# nigme1_Switch.net
KiCad netlist of a schematic drawn in Altium Designer
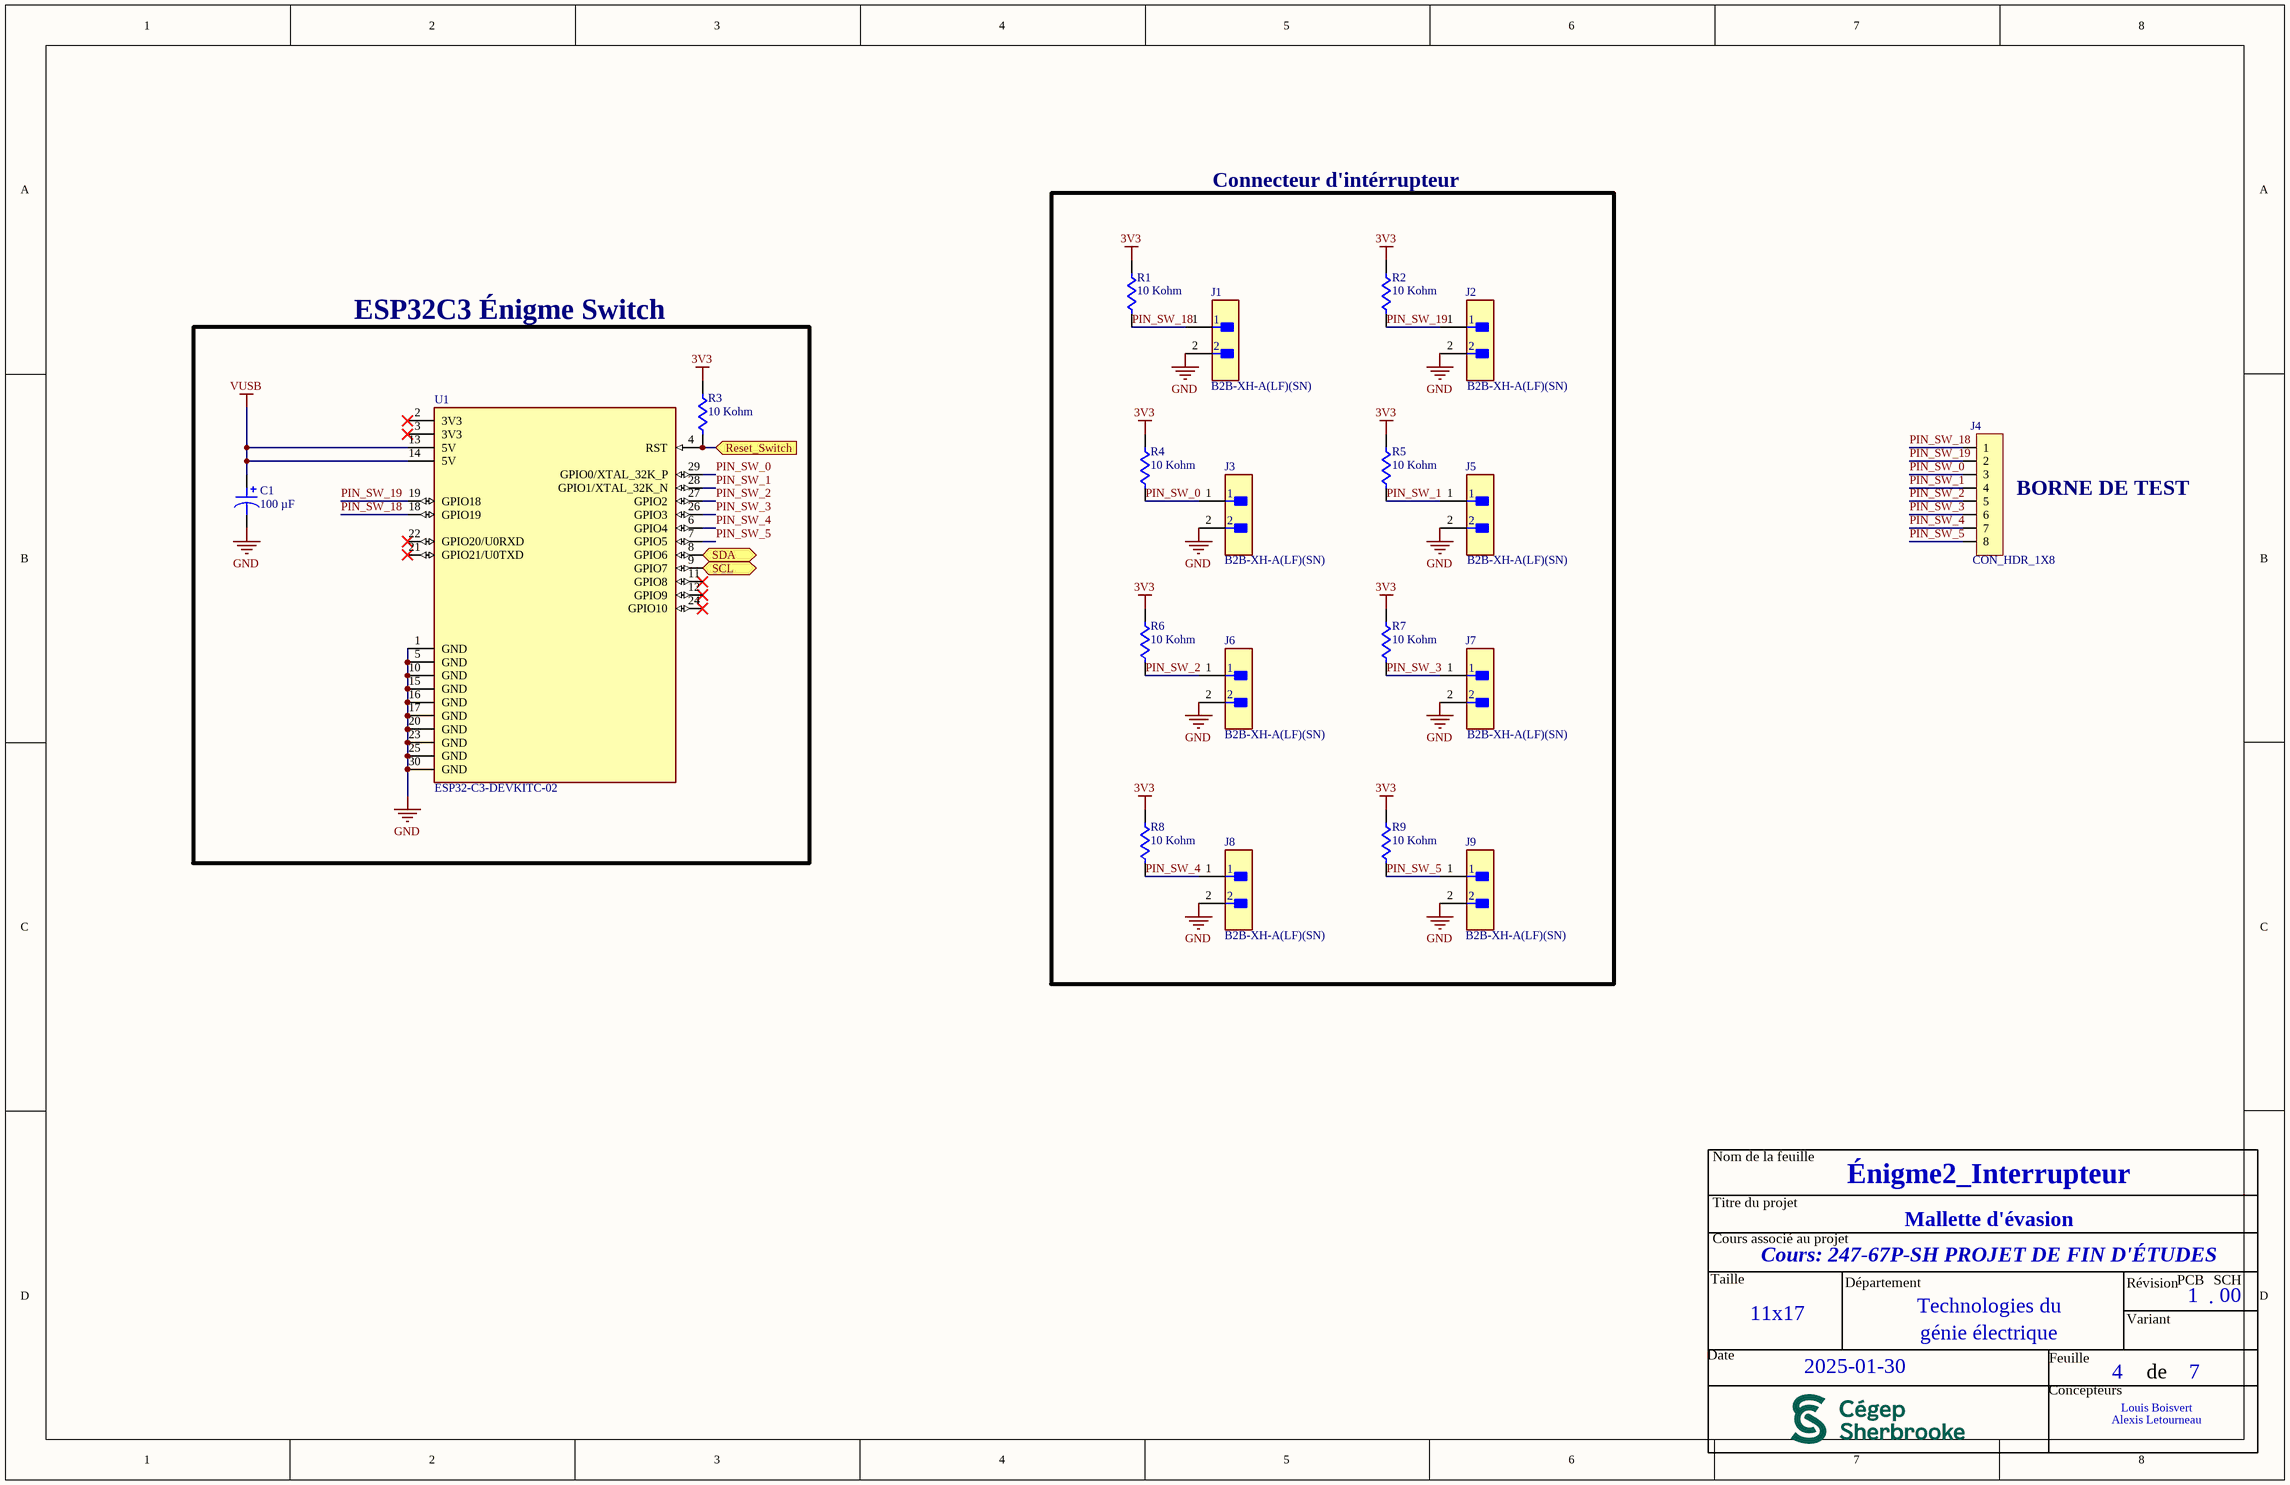
[diagram p0: Énigme1_Switch.SchDoc]

(export (version "E")
  (design (tool "Eeschema 10.0.6"))
  (components
    (comp (ref "C1")
      (value "100 µF")
      (footprint "CAP AL TH D8 L3.5 H12.5")
      (description "CAP ALUM 100UF 20% 50V RADIAL")
      (fields (field (name "PART NUMBER") "860020674015") (field (name "MANUFACTURER") "Würth Elektronik"))
      (libsource (lib "Celestial Altium Library - altium_library") (part "Polarised Capacitor"))
    )
    (comp (ref "J1")
      (value "B2B-XH-A(LF)(SN)")
      (footprint "FP-B2B-XH-A_LF_SN-MFG")
      (description "CONN HEADER VERT 2POS 2.5MM")
      (libsource (lib "Altium Content Vault") (part "3bc925449376181038e59eaffc5286c"))
    )
    (comp (ref "J2")
      (value "B2B-XH-A(LF)(SN)")
      (footprint "FP-B2B-XH-A_LF_SN-MFG")
      (description "CONN HEADER VERT 2POS 2.5MM")
      (libsource (lib "Altium Content Vault") (part "3bc925449376181038e59eaffc5286c"))
    )
    (comp (ref "J3")
      (value "B2B-XH-A(LF)(SN)")
      (footprint "FP-B2B-XH-A_LF_SN-MFG")
      (description "CONN HEADER VERT 2POS 2.5MM")
      (libsource (lib "Altium Content Vault") (part "3bc925449376181038e59eaffc5286c"))
    )
    (comp (ref "J4")
      (value "CON_HDR_1X8")
      (footprint "CON_HDR_1x8")
      (description "CON - Header 1X8 pins, 100Mils - TH-8")
      (fields (field (name "SOURCE") "CEGEP_SHERBROOKE_TGE_LIBRARY.SchLib"))
      (libsource (lib "Cegep de Sherbrooke") (part "CON_HDR_1X8"))
    )
    (comp (ref "J5")
      (value "B2B-XH-A(LF)(SN)")
      (footprint "FP-B2B-XH-A_LF_SN-MFG")
      (description "CONN HEADER VERT 2POS 2.5MM")
      (libsource (lib "Altium Content Vault") (part "3bc925449376181038e59eaffc5286c"))
    )
    (comp (ref "J6")
      (value "B2B-XH-A(LF)(SN)")
      (footprint "FP-B2B-XH-A_LF_SN-MFG")
      (description "CONN HEADER VERT 2POS 2.5MM")
      (libsource (lib "Altium Content Vault") (part "3bc925449376181038e59eaffc5286c"))
    )
    (comp (ref "J7")
      (value "B2B-XH-A(LF)(SN)")
      (footprint "FP-B2B-XH-A_LF_SN-MFG")
      (description "CONN HEADER VERT 2POS 2.5MM")
      (libsource (lib "Altium Content Vault") (part "3bc925449376181038e59eaffc5286c"))
    )
    (comp (ref "J8")
      (value "B2B-XH-A(LF)(SN)")
      (footprint "FP-B2B-XH-A_LF_SN-MFG")
      (description "CONN HEADER VERT 2POS 2.5MM")
      (libsource (lib "Altium Content Vault") (part "3bc925449376181038e59eaffc5286c"))
    )
    (comp (ref "J9")
      (value "B2B-XH-A(LF)(SN)")
      (footprint "FP-B2B-XH-A_LF_SN-MFG")
      (description "CONN HEADER VERT 2POS 2.5MM")
      (libsource (lib "Altium Content Vault") (part "3bc925449376181038e59eaffc5286c"))
    )
    (comp (ref "R1")
      (value "10 Kohm")
      (footprint "Res_Template")
      (description "Custom Semiconductor Resistor")
      (libsource (lib "Schlib1") (part "470 ohm"))
    )
    (comp (ref "R2")
      (value "10 Kohm")
      (footprint "Res_Template")
      (description "Custom Semiconductor Resistor")
      (libsource (lib "Schlib1") (part "470 ohm"))
    )
    (comp (ref "R3")
      (value "10 Kohm")
      (footprint "Res_Template")
      (description "Custom Semiconductor Resistor")
      (libsource (lib "Schlib1") (part "470 ohm"))
    )
    (comp (ref "R4")
      (value "10 Kohm")
      (footprint "Res_Template")
      (description "Custom Semiconductor Resistor")
      (libsource (lib "Schlib1") (part "470 ohm"))
    )
    (comp (ref "R5")
      (value "10 Kohm")
      (footprint "Res_Template")
      (description "Custom Semiconductor Resistor")
      (libsource (lib "Schlib1") (part "470 ohm"))
    )
    (comp (ref "R6")
      (value "10 Kohm")
      (footprint "Res_Template")
      (description "Custom Semiconductor Resistor")
      (libsource (lib "Schlib1") (part "470 ohm"))
    )
    (comp (ref "R7")
      (value "10 Kohm")
      (footprint "Res_Template")
      (description "Custom Semiconductor Resistor")
      (libsource (lib "Schlib1") (part "470 ohm"))
    )
    (comp (ref "R8")
      (value "10 Kohm")
      (footprint "Res_Template")
      (description "Custom Semiconductor Resistor")
      (libsource (lib "Schlib1") (part "470 ohm"))
    )
    (comp (ref "R9")
      (value "10 Kohm")
      (footprint "Res_Template")
      (description "Custom Semiconductor Resistor")
      (libsource (lib "Schlib1") (part "470 ohm"))
    )
    (comp (ref "U1")
      (value "ESP32-C3-DEVKITC-02")
      (footprint "XCVR_ESP32-C3-DEVKITC-02")
      (fields (field (name "MP") "ESP32-C3-DevKitC-02") (field (name "MF") "Espressif Systems"))
      (libsource (lib "ESP32-C3-DEVKITC-02") (part "ESP32-C3-DEVKITC-02"))
    )
  )
  (nets
    (net (code "1") (name "/PIN_SW_0") (class "Default")
      (node (ref "J3") (pin "1") (pinfunction "1_1") (pintype "passive"))
      (node (ref "J4") (pin "3") (pinfunction "3_3") (pintype "passive"))
      (node (ref "R4") (pin "1") (pinfunction "1_1") (pintype "passive"))
      (node (ref "U1") (pin "29") (pinfunction "GPIO0/XTAL_32K_P_29") (pintype "bidirectional"))
    )
    (net (code "2") (name "/PIN_SW_1") (class "Default")
      (node (ref "J4") (pin "4") (pinfunction "4_4") (pintype "passive"))
      (node (ref "J5") (pin "1") (pinfunction "1_1") (pintype "passive"))
      (node (ref "R5") (pin "1") (pinfunction "1_1") (pintype "passive"))
      (node (ref "U1") (pin "28") (pinfunction "GPIO1/XTAL_32K_N_28") (pintype "bidirectional"))
    )
    (net (code "3") (name "/PIN_SW_2") (class "Default")
      (node (ref "J4") (pin "5") (pinfunction "5_5") (pintype "passive"))
      (node (ref "J6") (pin "1") (pinfunction "1_1") (pintype "passive"))
      (node (ref "R6") (pin "1") (pinfunction "1_1") (pintype "passive"))
      (node (ref "U1") (pin "27") (pinfunction "GPIO2_27") (pintype "bidirectional"))
    )
    (net (code "4") (name "/PIN_SW_3") (class "Default")
      (node (ref "J4") (pin "6") (pinfunction "6_6") (pintype "passive"))
      (node (ref "J7") (pin "1") (pinfunction "1_1") (pintype "passive"))
      (node (ref "R7") (pin "1") (pinfunction "1_1") (pintype "passive"))
      (node (ref "U1") (pin "26") (pinfunction "GPIO3_26") (pintype "bidirectional"))
    )
    (net (code "5") (name "/PIN_SW_4") (class "Default")
      (node (ref "J4") (pin "7") (pinfunction "7_7") (pintype "passive"))
      (node (ref "J8") (pin "1") (pinfunction "1_1") (pintype "passive"))
      (node (ref "R8") (pin "1") (pinfunction "1_1") (pintype "passive"))
      (node (ref "U1") (pin "6") (pinfunction "GPIO4_6") (pintype "bidirectional"))
    )
    (net (code "6") (name "/PIN_SW_5") (class "Default")
      (node (ref "J4") (pin "8") (pinfunction "8_8") (pintype "passive"))
      (node (ref "J9") (pin "1") (pinfunction "1_1") (pintype "passive"))
      (node (ref "R9") (pin "1") (pinfunction "1_1") (pintype "passive"))
      (node (ref "U1") (pin "7") (pinfunction "GPIO5_7") (pintype "bidirectional"))
    )
    (net (code "7") (name "/PIN_SW_18") (class "Default")
      (node (ref "J1") (pin "1") (pinfunction "1_1") (pintype "passive"))
      (node (ref "J4") (pin "1") (pinfunction "1_1") (pintype "passive"))
      (node (ref "R1") (pin "1") (pinfunction "1_1") (pintype "passive"))
      (node (ref "U1") (pin "18") (pinfunction "GPIO19_18") (pintype "bidirectional"))
    )
    (net (code "8") (name "/PIN_SW_19") (class "Default")
      (node (ref "J2") (pin "1") (pinfunction "1_1") (pintype "passive"))
      (node (ref "J4") (pin "2") (pinfunction "2_2") (pintype "passive"))
      (node (ref "R2") (pin "1") (pinfunction "1_1") (pintype "passive"))
      (node (ref "U1") (pin "19") (pinfunction "GPIO18_19") (pintype "bidirectional"))
    )
    (net (code "9") (name "/Reset_Switch") (class "Default")
      (node (ref "R3") (pin "1") (pinfunction "1_1") (pintype "passive"))
      (node (ref "U1") (pin "4") (pinfunction "RST_4") (pintype "input"))
    )
    (net (code "10") (name "/SCL") (class "Default")
      (node (ref "U1") (pin "9") (pinfunction "GPIO7_9") (pintype "bidirectional"))
    )
    (net (code "11") (name "/SDA") (class "Default")
      (node (ref "U1") (pin "8") (pinfunction "GPIO6_8") (pintype "bidirectional"))
    )
    (net (code "12") (name "3V3") (class "Default")
      (node (ref "R1") (pin "2") (pinfunction "2_2") (pintype "passive"))
      (node (ref "R2") (pin "2") (pinfunction "2_2") (pintype "passive"))
      (node (ref "R3") (pin "2") (pinfunction "2_2") (pintype "passive"))
      (node (ref "R4") (pin "2") (pinfunction "2_2") (pintype "passive"))
      (node (ref "R5") (pin "2") (pinfunction "2_2") (pintype "passive"))
      (node (ref "R6") (pin "2") (pinfunction "2_2") (pintype "passive"))
      (node (ref "R7") (pin "2") (pinfunction "2_2") (pintype "passive"))
      (node (ref "R8") (pin "2") (pinfunction "2_2") (pintype "passive"))
      (node (ref "R9") (pin "2") (pinfunction "2_2") (pintype "passive"))
    )
    (net (code "13") (name "GND") (class "Default")
      (node (ref "C1") (pin "2") (pinfunction "2_2") (pintype "passive"))
      (node (ref "J1") (pin "2") (pinfunction "2_2") (pintype "passive"))
      (node (ref "J2") (pin "2") (pinfunction "2_2") (pintype "passive"))
      (node (ref "J3") (pin "2") (pinfunction "2_2") (pintype "passive"))
      (node (ref "J5") (pin "2") (pinfunction "2_2") (pintype "passive"))
      (node (ref "J6") (pin "2") (pinfunction "2_2") (pintype "passive"))
      (node (ref "J7") (pin "2") (pinfunction "2_2") (pintype "passive"))
      (node (ref "J8") (pin "2") (pinfunction "2_2") (pintype "passive"))
      (node (ref "J9") (pin "2") (pinfunction "2_2") (pintype "passive"))
      (node (ref "U1") (pin "1") (pinfunction "GND_1") (pintype "power_in"))
      (node (ref "U1") (pin "10") (pinfunction "GND_10") (pintype "power_in"))
      (node (ref "U1") (pin "15") (pinfunction "GND_15") (pintype "power_in"))
      (node (ref "U1") (pin "16") (pinfunction "GND_16") (pintype "power_in"))
      (node (ref "U1") (pin "17") (pinfunction "GND_17") (pintype "power_in"))
      (node (ref "U1") (pin "20") (pinfunction "GND_20") (pintype "power_in"))
      (node (ref "U1") (pin "23") (pinfunction "GND_23") (pintype "power_in"))
      (node (ref "U1") (pin "25") (pinfunction "GND_25") (pintype "power_in"))
      (node (ref "U1") (pin "30") (pinfunction "GND_30") (pintype "power_in"))
      (node (ref "U1") (pin "5") (pinfunction "GND_5") (pintype "power_in"))
    )
    (net (code "14") (name "VUSB") (class "Default")
      (node (ref "C1") (pin "1") (pinfunction "1_1") (pintype "passive"))
      (node (ref "U1") (pin "13") (pinfunction "5V_13") (pintype "power_in"))
      (node (ref "U1") (pin "14") (pinfunction "5V_14") (pintype "power_in"))
    )
    (net (code "15") (name "unconnected-(U1-3V3-Pad2)") (class "Default")
      (node (ref "U1") (pin "2") (pinfunction "3V3_2") (pintype "power_in+no_connect"))
    )
    (net (code "16") (name "unconnected-(U1-3V3-Pad3)") (class "Default")
      (node (ref "U1") (pin "3") (pinfunction "3V3_3") (pintype "power_in+no_connect"))
    )
    (net (code "17") (name "unconnected-(U1-GPIO8-Pad11)") (class "Default")
      (node (ref "U1") (pin "11") (pinfunction "GPIO8_11") (pintype "bidirectional+no_connect"))
    )
    (net (code "18") (name "unconnected-(U1-GPIO9-Pad12)") (class "Default")
      (node (ref "U1") (pin "12") (pinfunction "GPIO9_12") (pintype "bidirectional+no_connect"))
    )
    (net (code "19") (name "unconnected-(U1-GPIO10-Pad24)") (class "Default")
      (node (ref "U1") (pin "24") (pinfunction "GPIO10_24") (pintype "bidirectional+no_connect"))
    )
    (net (code "20") (name "unconnected-(U1-GPIO20{slash}U0RXD-Pad22)") (class "Default")
      (node (ref "U1") (pin "22") (pinfunction "GPIO20/U0RXD_22") (pintype "bidirectional+no_connect"))
    )
    (net (code "21") (name "unconnected-(U1-GPIO21{slash}U0TXD-Pad21)") (class "Default")
      (node (ref "U1") (pin "21") (pinfunction "GPIO21/U0TXD_21") (pintype "bidirectional+no_connect"))
    )
  )
)
